# hk310.net
KiCad netlist of a schematic drawn in EAGLE
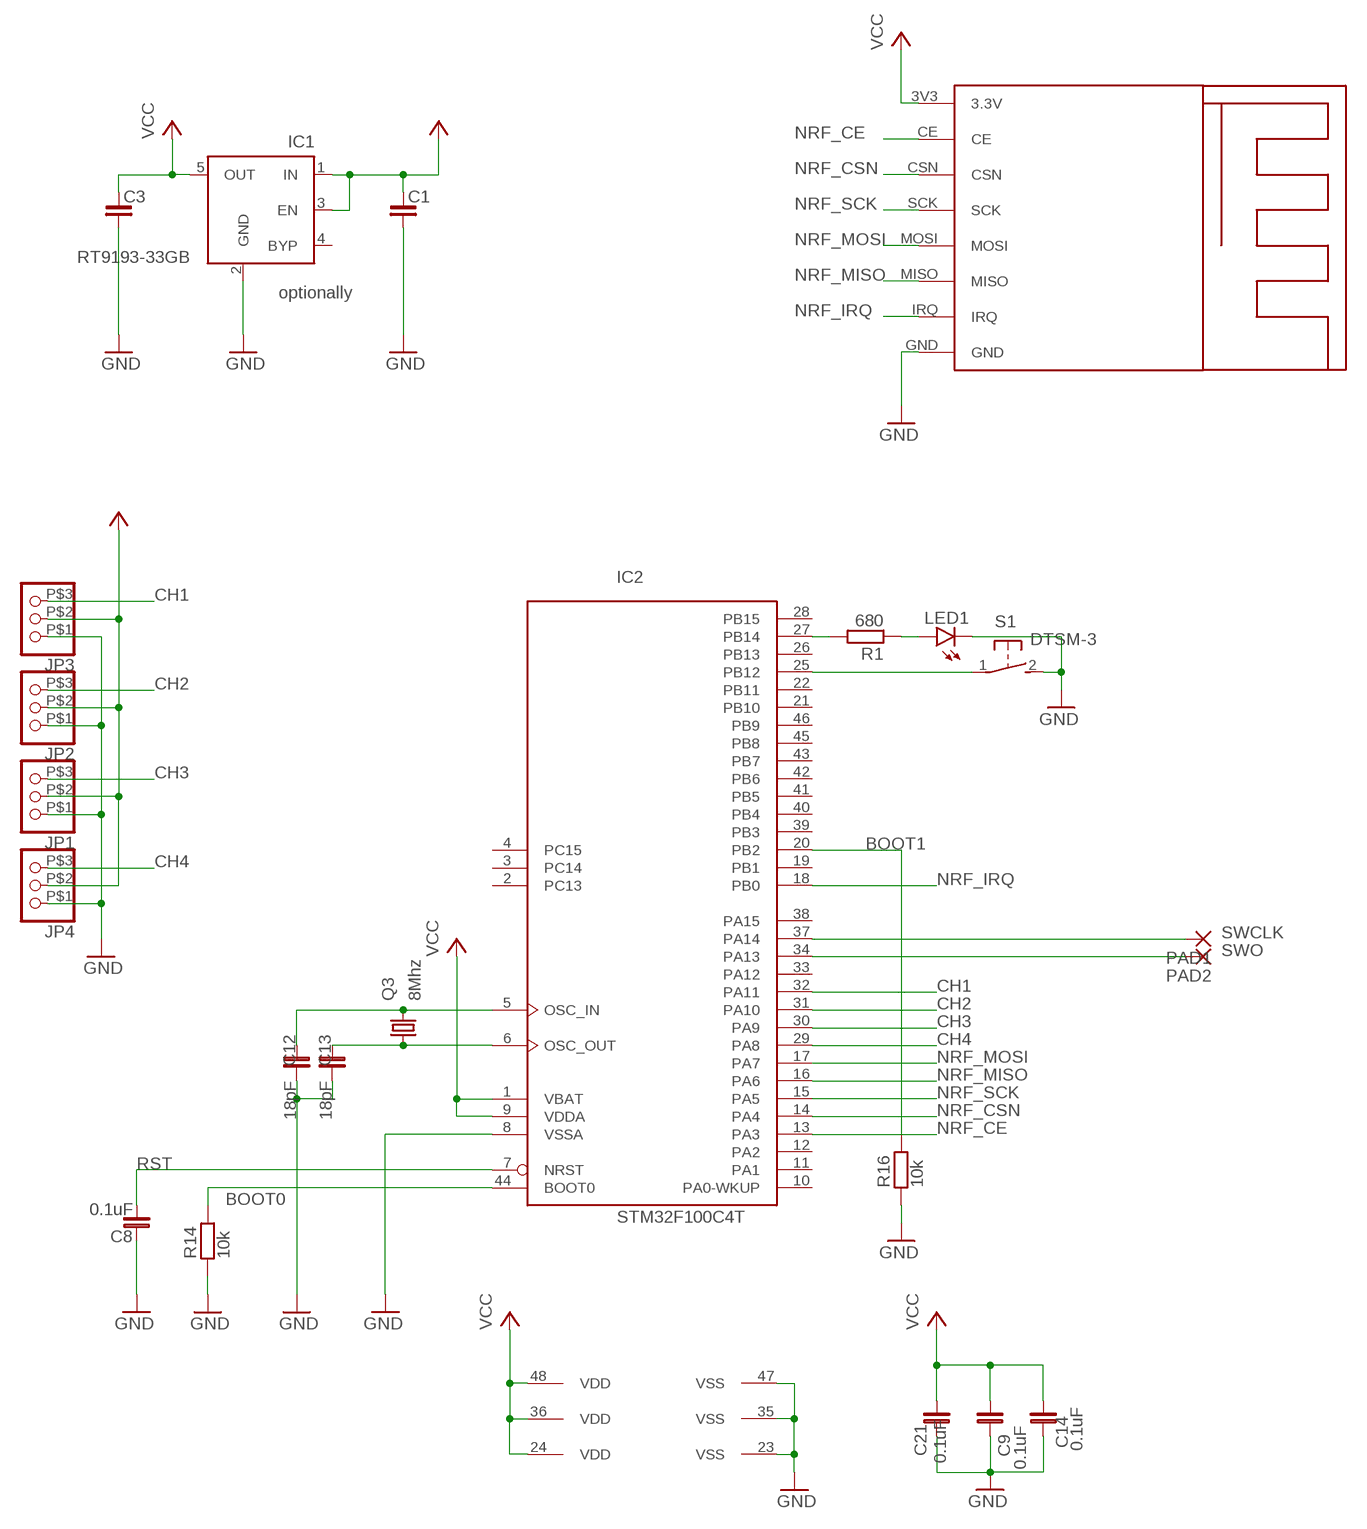
[diagram p0: schematic, sheet 1]

(export (version "E")
  (design (tool "Eeschema 10.0.6"))
  (components
    (comp (ref "C1")
      (value "C_0805")
      (footprint "eagle-import:C0805")
      (libsource (lib "eagle-import") (part "C_0805"))
    )
    (comp (ref "C3")
      (value "C_0805")
      (footprint "eagle-import:C0805")
      (libsource (lib "eagle-import") (part "C_0805"))
    )
    (comp (ref "C8")
      (value "0.1uF")
      (footprint "eagle-import:C0603")
      (libsource (lib "eagle-import") (part "C_0603"))
    )
    (comp (ref "C9")
      (value "0.1uF")
      (footprint "eagle-import:C0603")
      (libsource (lib "eagle-import") (part "C_0603"))
    )
    (comp (ref "C12")
      (value "18pF")
      (footprint "eagle-import:C0603")
      (libsource (lib "eagle-import") (part "C_0603"))
    )
    (comp (ref "C13")
      (value "18pF")
      (footprint "eagle-import:C0603")
      (libsource (lib "eagle-import") (part "C_0603"))
    )
    (comp (ref "C14")
      (value "0.1uF")
      (footprint "eagle-import:C0603")
      (libsource (lib "eagle-import") (part "C_0603"))
    )
    (comp (ref "C21")
      (value "0.1uF")
      (footprint "eagle-import:C0603")
      (libsource (lib "eagle-import") (part "C_0603"))
    )
    (comp (ref "IC1")
      (value "RT9193-33GB")
      (footprint "eagle-import:SOT23-5")
      (libsource (lib "eagle-import") (part "MIC5219XX"))
    )
    (comp (ref "IC2")
      (value "STM32F100C4T")
      (footprint "eagle-import:LQFP48")
      (libsource (lib "eagle-import") (part "STM32F100CT4"))
    )
    (comp (ref "JP1")
      (value "PINHD-1X3")
      (footprint "eagle-import:1X03")
      (libsource (lib "eagle-import") (part "PINHD-1X3"))
    )
    (comp (ref "JP2")
      (value "PINHD-1X3")
      (footprint "eagle-import:1X03")
      (libsource (lib "eagle-import") (part "PINHD-1X3"))
    )
    (comp (ref "JP3")
      (value "PINHD-1X3")
      (footprint "eagle-import:1X03")
      (libsource (lib "eagle-import") (part "PINHD-1X3"))
    )
    (comp (ref "JP4")
      (value "PINHD-1X3")
      (footprint "eagle-import:1X03")
      (libsource (lib "eagle-import") (part "PINHD-1X3"))
    )
    (comp (ref "LED1")
      (value "LED")
      (footprint "eagle-import:SMARTLED-TTW")
      (libsource (lib "eagle-import") (part "LED"))
    )
    (comp (ref "PAD1")
      (value "SMD2")
      (footprint "eagle-import:SMD1,27-2,54")
      (libsource (lib "eagle-import") (part "SMD2"))
    )
    (comp (ref "PAD2")
      (value "SMD2")
      (footprint "eagle-import:SMD1,27-2,54")
      (libsource (lib "eagle-import") (part "SMD2"))
    )
    (comp (ref "Q3")
      (value "8Mhz")
      (footprint "eagle-import:6.0X3.5_2")
      (libsource (lib "eagle-import") (part "KX-12B"))
    )
    (comp (ref "R1")
      (value "680")
      (footprint "eagle-import:R0805")
      (libsource (lib "eagle-import") (part "R_0805"))
    )
    (comp (ref "R14")
      (value "10k")
      (footprint "eagle-import:R0805")
      (libsource (lib "eagle-import") (part "R_0805"))
    )
    (comp (ref "R16")
      (value "10k")
      (footprint "eagle-import:R0805")
      (libsource (lib "eagle-import") (part "R_0805"))
    )
    (comp (ref "S1")
      (value "DTSM-3")
      (footprint "eagle-import:DTSM-3")
      (libsource (lib "eagle-import") (part "DTSM-3"))
    )
    (comp (ref "U$1")
      (value "NRF24MINI")
      (footprint "eagle-import:NRF24MINI")
      (libsource (lib "eagle-import") (part "NRF24MINI"))
    )
  )
  (nets
    (net (code "1") (name "+5V") (class "Default")
      (node (ref "C1") (pin "1") (pinfunction "1_1") (pintype "passive"))
      (node (ref "IC1") (pin "1") (pinfunction "IN_1") (pintype "input"))
      (node (ref "IC1") (pin "3") (pinfunction "EN_3") (pintype "input"))
      (node (ref "JP1") (pin "P$2") (pinfunction "2_P$2") (pintype "passive"))
      (node (ref "JP2") (pin "P$2") (pinfunction "2_P$2") (pintype "passive"))
      (node (ref "JP3") (pin "P$2") (pinfunction "2_P$2") (pintype "passive"))
      (node (ref "JP4") (pin "P$2") (pinfunction "2_P$2") (pintype "passive"))
    )
    (net (code "2") (name "/BOOT0") (class "Default")
      (node (ref "IC2") (pin "44") (pinfunction "BOOT0_44") (pintype "input"))
      (node (ref "R14") (pin "2") (pinfunction "2_2") (pintype "passive"))
    )
    (net (code "3") (name "/BOOT1") (class "Default")
      (node (ref "IC2") (pin "20") (pinfunction "PB2_20") (pintype "bidirectional"))
      (node (ref "R16") (pin "2") (pinfunction "2_2") (pintype "passive"))
    )
    (net (code "4") (name "/CH1") (class "Default")
      (node (ref "IC2") (pin "32") (pinfunction "PA11_32") (pintype "bidirectional"))
      (node (ref "JP3") (pin "P$3") (pinfunction "3_P$3") (pintype "passive"))
    )
    (net (code "5") (name "/CH2") (class "Default")
      (node (ref "IC2") (pin "31") (pinfunction "PA10_31") (pintype "bidirectional"))
      (node (ref "JP2") (pin "P$3") (pinfunction "3_P$3") (pintype "passive"))
    )
    (net (code "6") (name "/CH3") (class "Default")
      (node (ref "IC2") (pin "30") (pinfunction "PA9_30") (pintype "bidirectional"))
      (node (ref "JP1") (pin "P$3") (pinfunction "3_P$3") (pintype "passive"))
    )
    (net (code "7") (name "/CH4") (class "Default")
      (node (ref "IC2") (pin "29") (pinfunction "PA8_29") (pintype "bidirectional"))
      (node (ref "JP4") (pin "P$3") (pinfunction "3_P$3") (pintype "passive"))
    )
    (net (code "8") (name "/NRF_CE") (class "Default")
      (node (ref "IC2") (pin "13") (pinfunction "PA3_13") (pintype "bidirectional"))
      (node (ref "U$1") (pin "CE") (pinfunction "CE_CE") (pintype "bidirectional"))
    )
    (net (code "9") (name "/NRF_CSN") (class "Default")
      (node (ref "IC2") (pin "14") (pinfunction "PA4_14") (pintype "bidirectional"))
      (node (ref "U$1") (pin "CSN") (pinfunction "CSN_CSN") (pintype "bidirectional"))
    )
    (net (code "10") (name "/NRF_IRQ") (class "Default")
      (node (ref "IC2") (pin "18") (pinfunction "PB0_18") (pintype "bidirectional"))
      (node (ref "U$1") (pin "IRQ") (pinfunction "IRQ_IRQ") (pintype "bidirectional"))
    )
    (net (code "11") (name "/NRF_MISO") (class "Default")
      (node (ref "IC2") (pin "16") (pinfunction "PA6_16") (pintype "bidirectional"))
      (node (ref "U$1") (pin "MISO") (pinfunction "MISO_MISO") (pintype "bidirectional"))
    )
    (net (code "12") (name "/NRF_MOSI") (class "Default")
      (node (ref "IC2") (pin "17") (pinfunction "PA7_17") (pintype "bidirectional"))
      (node (ref "U$1") (pin "MOSI") (pinfunction "MOSI_MOSI") (pintype "bidirectional"))
    )
    (net (code "13") (name "/NRF_SCK") (class "Default")
      (node (ref "IC2") (pin "15") (pinfunction "PA5_15") (pintype "bidirectional"))
      (node (ref "U$1") (pin "SCK") (pinfunction "SCK_SCK") (pintype "bidirectional"))
    )
    (net (code "14") (name "/RST") (class "Default")
      (node (ref "C8") (pin "2") (pinfunction "2_2") (pintype "passive"))
      (node (ref "IC2") (pin "7") (pinfunction "NRST_7") (pintype "bidirectional"))
    )
    (net (code "15") (name "/SWCLK") (class "Default")
      (node (ref "IC2") (pin "37") (pinfunction "PA14_37") (pintype "bidirectional"))
      (node (ref "PAD1") (pin "1") (pinfunction "P_1") (pintype "passive"))
    )
    (net (code "16") (name "/SWO") (class "Default")
      (node (ref "IC2") (pin "34") (pinfunction "PA13_34") (pintype "bidirectional"))
      (node (ref "PAD2") (pin "1") (pinfunction "P_1") (pintype "passive"))
    )
    (net (code "17") (name "GND") (class "Default")
      (node (ref "C1") (pin "2") (pinfunction "2_2") (pintype "passive"))
      (node (ref "C12") (pin "1") (pinfunction "1_1") (pintype "passive"))
      (node (ref "C13") (pin "1") (pinfunction "1_1") (pintype "passive"))
      (node (ref "C14") (pin "1") (pinfunction "1_1") (pintype "passive"))
      (node (ref "C21") (pin "1") (pinfunction "1_1") (pintype "passive"))
      (node (ref "C3") (pin "2") (pinfunction "2_2") (pintype "passive"))
      (node (ref "C8") (pin "1") (pinfunction "1_1") (pintype "passive"))
      (node (ref "C9") (pin "1") (pinfunction "1_1") (pintype "passive"))
      (node (ref "IC1") (pin "2") (pinfunction "GND_2") (pintype "power_in"))
      (node (ref "IC2") (pin "23") (pinfunction "VSS_23") (pintype "power_in"))
      (node (ref "IC2") (pin "35") (pinfunction "VSS_35") (pintype "power_in"))
      (node (ref "IC2") (pin "47") (pinfunction "VSS_47") (pintype "power_in"))
      (node (ref "IC2") (pin "8") (pinfunction "VSSA_8") (pintype "power_in"))
      (node (ref "JP1") (pin "P$1") (pinfunction "1_P$1") (pintype "passive"))
      (node (ref "JP2") (pin "P$1") (pinfunction "1_P$1") (pintype "passive"))
      (node (ref "JP3") (pin "P$1") (pinfunction "1_P$1") (pintype "passive"))
      (node (ref "JP4") (pin "P$1") (pinfunction "1_P$1") (pintype "passive"))
      (node (ref "LED1") (pin "C@1") (pinfunction "C_C@1") (pintype "passive"))
      (node (ref "R14") (pin "1") (pinfunction "1_1") (pintype "passive"))
      (node (ref "R16") (pin "1") (pinfunction "1_1") (pintype "passive"))
      (node (ref "S1") (pin "2") (pinfunction "2_2") (pintype "passive"))
      (node (ref "U$1") (pin "GND") (pinfunction "GND_GND") (pintype "bidirectional"))
    )
    (net (code "18") (name "Net-(IC2A-OSC_IN)") (class "Default")
      (node (ref "C12") (pin "2") (pinfunction "2_2") (pintype "passive"))
      (node (ref "IC2") (pin "5") (pinfunction "OSC_IN_5") (pintype "bidirectional"))
      (node (ref "Q3") (pin "2") (pinfunction "2_2") (pintype "passive"))
    )
    (net (code "19") (name "Net-(IC2A-OSC_OUT)") (class "Default")
      (node (ref "C13") (pin "2") (pinfunction "2_2") (pintype "passive"))
      (node (ref "IC2") (pin "6") (pinfunction "OSC_OUT_6") (pintype "bidirectional"))
      (node (ref "Q3") (pin "1") (pinfunction "1_1") (pintype "passive"))
    )
    (net (code "20") (name "Net-(IC2A-PB12)") (class "Default")
      (node (ref "IC2") (pin "25") (pinfunction "PB12_25") (pintype "bidirectional"))
      (node (ref "S1") (pin "1") (pinfunction "1_1") (pintype "passive"))
    )
    (net (code "21") (name "Net-(IC2A-PB14)") (class "Default")
      (node (ref "IC2") (pin "27") (pinfunction "PB14_27") (pintype "bidirectional"))
      (node (ref "R1") (pin "2") (pinfunction "2_2") (pintype "passive"))
    )
    (net (code "22") (name "Net-(LED1-A)") (class "Default")
      (node (ref "LED1") (pin "A@1") (pinfunction "A_A@1") (pintype "passive"))
      (node (ref "R1") (pin "1") (pinfunction "1_1") (pintype "passive"))
    )
    (net (code "23") (name "VCC") (class "Default")
      (node (ref "C14") (pin "2") (pinfunction "2_2") (pintype "passive"))
      (node (ref "C21") (pin "2") (pinfunction "2_2") (pintype "passive"))
      (node (ref "C3") (pin "1") (pinfunction "1_1") (pintype "passive"))
      (node (ref "C9") (pin "2") (pinfunction "2_2") (pintype "passive"))
      (node (ref "IC1") (pin "5") (pinfunction "OUT_5") (pintype "output"))
      (node (ref "IC2") (pin "1") (pinfunction "VBAT_1") (pintype "power_in"))
      (node (ref "IC2") (pin "24") (pinfunction "VDD_24") (pintype "power_in"))
      (node (ref "IC2") (pin "36") (pinfunction "VDD_36") (pintype "power_in"))
      (node (ref "IC2") (pin "48") (pinfunction "VDD_48") (pintype "power_in"))
      (node (ref "IC2") (pin "9") (pinfunction "VDDA_9") (pintype "power_in"))
      (node (ref "U$1") (pin "3V3") (pinfunction "3.3V_3V3") (pintype "bidirectional"))
    )
    (net (code "24") (name "unconnected-(IC1-BYP-Pad4)") (class "Default")
      (node (ref "IC1") (pin "4") (pinfunction "BYP_4") (pintype "passive"))
    )
    (net (code "25") (name "unconnected-(IC2A-PA0-WKUP-Pad10)") (class "Default")
      (node (ref "IC2") (pin "10") (pinfunction "PA0-WKUP_10") (pintype "bidirectional"))
    )
    (net (code "26") (name "unconnected-(IC2A-PA1-Pad11)") (class "Default")
      (node (ref "IC2") (pin "11") (pinfunction "PA1_11") (pintype "bidirectional"))
    )
    (net (code "27") (name "unconnected-(IC2A-PA2-Pad12)") (class "Default")
      (node (ref "IC2") (pin "12") (pinfunction "PA2_12") (pintype "bidirectional"))
    )
    (net (code "28") (name "unconnected-(IC2A-PA12-Pad33)") (class "Default")
      (node (ref "IC2") (pin "33") (pinfunction "PA12_33") (pintype "bidirectional"))
    )
    (net (code "29") (name "unconnected-(IC2A-PA15-Pad38)") (class "Default")
      (node (ref "IC2") (pin "38") (pinfunction "PA15_38") (pintype "bidirectional"))
    )
    (net (code "30") (name "unconnected-(IC2A-PB1-Pad19)") (class "Default")
      (node (ref "IC2") (pin "19") (pinfunction "PB1_19") (pintype "bidirectional"))
    )
    (net (code "31") (name "unconnected-(IC2A-PB3-Pad39)") (class "Default")
      (node (ref "IC2") (pin "39") (pinfunction "PB3_39") (pintype "bidirectional"))
    )
    (net (code "32") (name "unconnected-(IC2A-PB4-Pad40)") (class "Default")
      (node (ref "IC2") (pin "40") (pinfunction "PB4_40") (pintype "bidirectional"))
    )
    (net (code "33") (name "unconnected-(IC2A-PB5-Pad41)") (class "Default")
      (node (ref "IC2") (pin "41") (pinfunction "PB5_41") (pintype "bidirectional"))
    )
    (net (code "34") (name "unconnected-(IC2A-PB6-Pad42)") (class "Default")
      (node (ref "IC2") (pin "42") (pinfunction "PB6_42") (pintype "bidirectional"))
    )
    (net (code "35") (name "unconnected-(IC2A-PB7-Pad43)") (class "Default")
      (node (ref "IC2") (pin "43") (pinfunction "PB7_43") (pintype "bidirectional"))
    )
    (net (code "36") (name "unconnected-(IC2A-PB8-Pad45)") (class "Default")
      (node (ref "IC2") (pin "45") (pinfunction "PB8_45") (pintype "bidirectional"))
    )
    (net (code "37") (name "unconnected-(IC2A-PB9-Pad46)") (class "Default")
      (node (ref "IC2") (pin "46") (pinfunction "PB9_46") (pintype "bidirectional"))
    )
    (net (code "38") (name "unconnected-(IC2A-PB10-Pad21)") (class "Default")
      (node (ref "IC2") (pin "21") (pinfunction "PB10_21") (pintype "bidirectional"))
    )
    (net (code "39") (name "unconnected-(IC2A-PB11-Pad22)") (class "Default")
      (node (ref "IC2") (pin "22") (pinfunction "PB11_22") (pintype "bidirectional"))
    )
    (net (code "40") (name "unconnected-(IC2A-PB13-Pad26)") (class "Default")
      (node (ref "IC2") (pin "26") (pinfunction "PB13_26") (pintype "bidirectional"))
    )
    (net (code "41") (name "unconnected-(IC2A-PB15-Pad28)") (class "Default")
      (node (ref "IC2") (pin "28") (pinfunction "PB15_28") (pintype "bidirectional"))
    )
    (net (code "42") (name "unconnected-(IC2A-PC13-Pad2)") (class "Default")
      (node (ref "IC2") (pin "2") (pinfunction "PC13_2") (pintype "bidirectional"))
    )
    (net (code "43") (name "unconnected-(IC2A-PC14-Pad3)") (class "Default")
      (node (ref "IC2") (pin "3") (pinfunction "PC14_3") (pintype "bidirectional"))
    )
    (net (code "44") (name "unconnected-(IC2A-PC15-Pad4)") (class "Default")
      (node (ref "IC2") (pin "4") (pinfunction "PC15_4") (pintype "bidirectional"))
    )
  )
)
